# TDA2040_Amp_v2_2.net
KiCad netlist of a schematic drawn in EAGLE
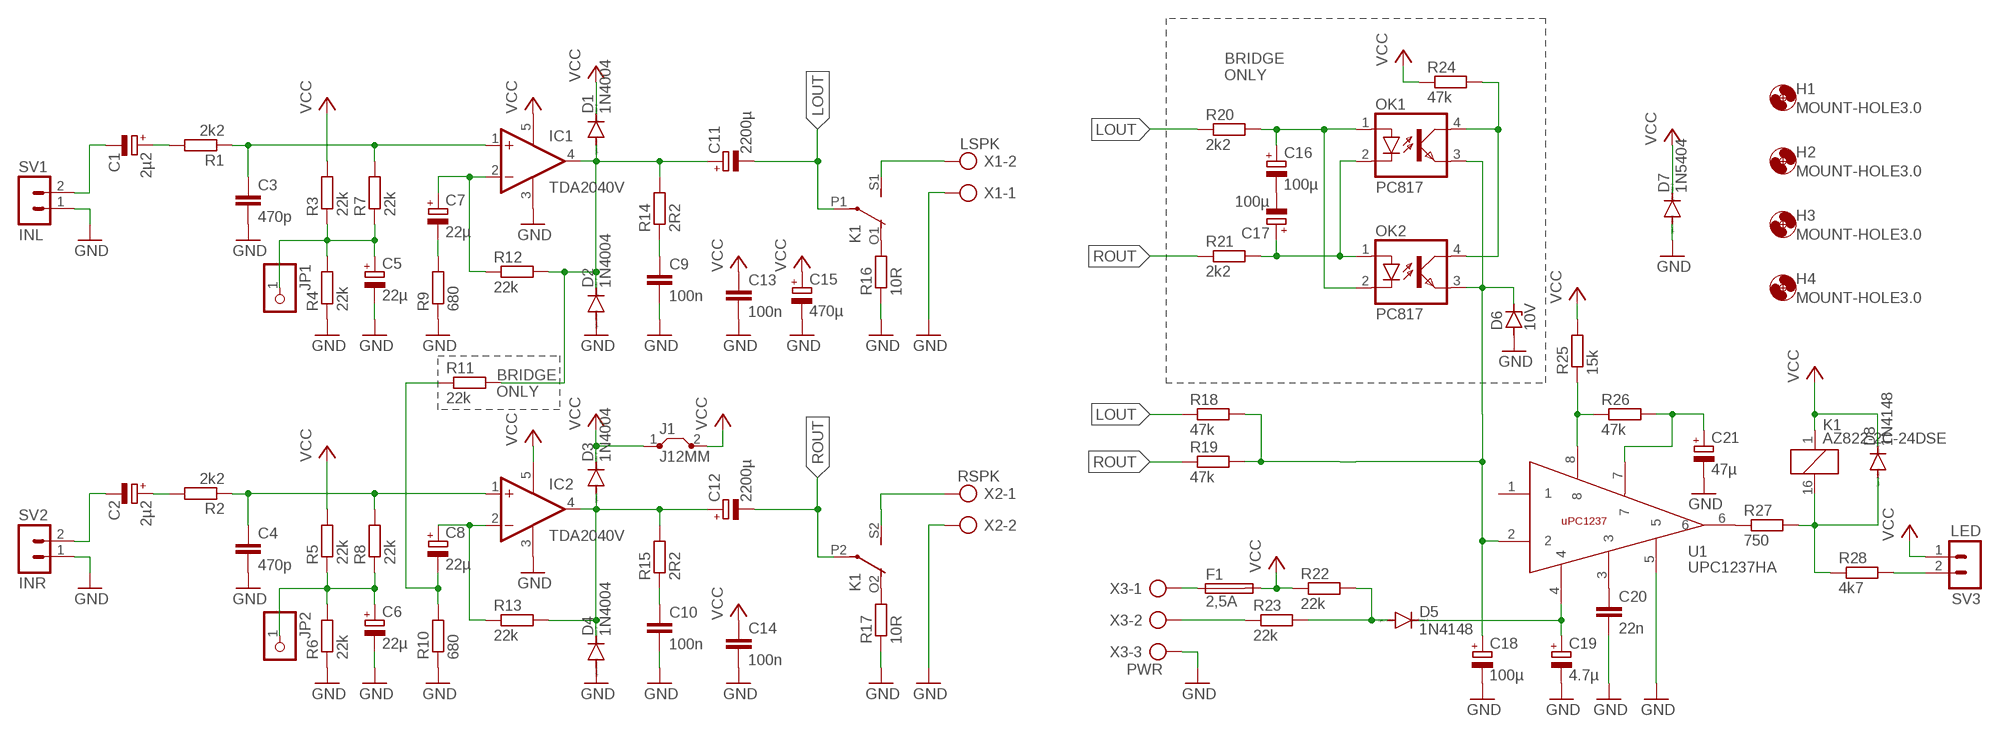
[diagram p0: schematic, sheet 1]

(export (version "E")
  (design (tool "Eeschema 10.0.6"))
  (components
    (comp (ref "C1")
      (value "2µ2")
      (footprint "eagle-import:E2,5-5")
      (libsource (lib "eagle-import") (part "CPOL-EUE2.5-5"))
    )
    (comp (ref "C2")
      (value "2µ2")
      (footprint "eagle-import:E2,5-5")
      (libsource (lib "eagle-import") (part "CPOL-EUE2.5-5"))
    )
    (comp (ref "C3")
      (value "470p")
      (footprint "eagle-import:C050-024X044")
      (libsource (lib "eagle-import") (part "C-EU050-024X044"))
    )
    (comp (ref "C4")
      (value "470p")
      (footprint "eagle-import:C050-024X044")
      (libsource (lib "eagle-import") (part "C-EU050-024X044"))
    )
    (comp (ref "C5")
      (value "22µ")
      (footprint "eagle-import:E2,5-6")
      (libsource (lib "eagle-import") (part "CPOL-EUE2.5-6"))
    )
    (comp (ref "C6")
      (value "22µ")
      (footprint "eagle-import:E2,5-6")
      (libsource (lib "eagle-import") (part "CPOL-EUE2.5-6"))
    )
    (comp (ref "C7")
      (value "22µ")
      (footprint "eagle-import:E2,5-6")
      (libsource (lib "eagle-import") (part "CPOL-EUE2.5-6"))
    )
    (comp (ref "C8")
      (value "22µ")
      (footprint "eagle-import:E2,5-6")
      (libsource (lib "eagle-import") (part "CPOL-EUE2.5-6"))
    )
    (comp (ref "C9")
      (value "100n")
      (footprint "eagle-import:C050-024X044")
      (libsource (lib "eagle-import") (part "C-EU050-024X044"))
    )
    (comp (ref "C10")
      (value "100n")
      (footprint "eagle-import:C050-024X044")
      (libsource (lib "eagle-import") (part "C-EU050-024X044"))
    )
    (comp (ref "C11")
      (value "2200µ")
      (footprint "eagle-import:E5-13")
      (libsource (lib "eagle-import") (part "CPOL-EUE5-13"))
    )
    (comp (ref "C12")
      (value "2200µ")
      (footprint "eagle-import:E5-13")
      (libsource (lib "eagle-import") (part "CPOL-EUE5-13"))
    )
    (comp (ref "C13")
      (value "100n")
      (footprint "eagle-import:C050-024X044")
      (libsource (lib "eagle-import") (part "C-EU050-024X044"))
    )
    (comp (ref "C14")
      (value "100n")
      (footprint "eagle-import:C050-024X044")
      (libsource (lib "eagle-import") (part "C-EU050-024X044"))
    )
    (comp (ref "C15")
      (value "470µ")
      (footprint "eagle-import:E5-13")
      (libsource (lib "eagle-import") (part "CPOL-EUE5-13"))
    )
    (comp (ref "C16")
      (value "100µ")
      (footprint "eagle-import:E2,5-6")
      (libsource (lib "eagle-import") (part "CPOL-EUE2.5-6"))
    )
    (comp (ref "C17")
      (value "100µ")
      (footprint "eagle-import:E2,5-6")
      (libsource (lib "eagle-import") (part "CPOL-EUE2.5-6"))
    )
    (comp (ref "C18")
      (value "100µ")
      (footprint "eagle-import:E2,5-5")
      (libsource (lib "eagle-import") (part "CPOL-EUE2.5-5"))
    )
    (comp (ref "C19")
      (value "4.7µ")
      (footprint "eagle-import:E2,5-5")
      (libsource (lib "eagle-import") (part "CPOL-EUE2.5-5"))
    )
    (comp (ref "C20")
      (value "22n")
      (footprint "eagle-import:C050-024X044")
      (libsource (lib "eagle-import") (part "C-EU050-024X044"))
    )
    (comp (ref "C21")
      (value "47µ")
      (footprint "eagle-import:E2,5-5")
      (libsource (lib "eagle-import") (part "CPOL-EUE2.5-5"))
    )
    (comp (ref "D1")
      (value "1N4004")
      (footprint "eagle-import:DO41-10")
      (libsource (lib "eagle-import") (part "1N4004"))
    )
    (comp (ref "D2")
      (value "1N4004")
      (footprint "eagle-import:DO41-10")
      (libsource (lib "eagle-import") (part "1N4004"))
    )
    (comp (ref "D3")
      (value "1N4004")
      (footprint "eagle-import:DO41-10")
      (libsource (lib "eagle-import") (part "1N4004"))
    )
    (comp (ref "D4")
      (value "1N4004")
      (footprint "eagle-import:DO41-10")
      (libsource (lib "eagle-import") (part "1N4004"))
    )
    (comp (ref "D5")
      (value "1N4148")
      (footprint "eagle-import:DO35-7")
      (libsource (lib "eagle-import") (part "1N4148DO35-7"))
    )
    (comp (ref "D6")
      (value "10V")
      (footprint "eagle-import:DO34Z7")
      (libsource (lib "eagle-import") (part "ZENER-DIODEDO34-7"))
    )
    (comp (ref "D7")
      (value "1N5404")
      (footprint "eagle-import:DO201-15")
      (libsource (lib "eagle-import") (part "1N5400"))
    )
    (comp (ref "D8")
      (value "1N4148")
      (footprint "eagle-import:DO35-7")
      (libsource (lib "eagle-import") (part "1N4148DO35-7"))
    )
    (comp (ref "F1")
      (value "2,5A")
      (footprint "eagle-import:SH22")
      (libsource (lib "eagle-import") (part "SH22"))
    )
    (comp (ref "H1")
      (value "MOUNT-HOLE3.0")
      (footprint "eagle-import:3,0")
      (libsource (lib "eagle-import") (part "MOUNT-HOLE3.0"))
    )
    (comp (ref "H2")
      (value "MOUNT-HOLE3.0")
      (footprint "eagle-import:3,0")
      (libsource (lib "eagle-import") (part "MOUNT-HOLE3.0"))
    )
    (comp (ref "H3")
      (value "MOUNT-HOLE3.0")
      (footprint "eagle-import:3,0")
      (libsource (lib "eagle-import") (part "MOUNT-HOLE3.0"))
    )
    (comp (ref "H4")
      (value "MOUNT-HOLE3.0")
      (footprint "eagle-import:3,0")
      (libsource (lib "eagle-import") (part "MOUNT-HOLE3.0"))
    )
    (comp (ref "IC1")
      (value "TDA2040V")
      (footprint "eagle-import:CB360")
      (libsource (lib "eagle-import") (part "TDA2040V"))
    )
    (comp (ref "IC2")
      (value "TDA2040V")
      (footprint "eagle-import:CB360")
      (libsource (lib "eagle-import") (part "TDA2040V"))
    )
    (comp (ref "J1")
      (value "J12MM")
      (footprint "eagle-import:12")
      (libsource (lib "eagle-import") (part "J12MM"))
    )
    (comp (ref "JP1")
      (value "PINHD-1X1A")
      (footprint "eagle-import:1X01A")
      (libsource (lib "eagle-import") (part "PINHD-1X1A"))
    )
    (comp (ref "JP2")
      (value "PINHD-1X1A")
      (footprint "eagle-import:1X01A")
      (libsource (lib "eagle-import") (part "PINHD-1X1A"))
    )
    (comp (ref "K1")
      (value "AZ822-2C-24DSE")
      (footprint "eagle-import:351")
      (libsource (lib "eagle-import") (part "351"))
    )
    (comp (ref "OK1")
      (value "PC817")
      (footprint "eagle-import:DIL04")
      (fields (field (name "MPN") "PC817X4J000F"))
      (libsource (lib "eagle-import") (part "PC817"))
    )
    (comp (ref "OK2")
      (value "PC817")
      (footprint "eagle-import:DIL04")
      (fields (field (name "MPN") "PC817X4J000F"))
      (libsource (lib "eagle-import") (part "PC817"))
    )
    (comp (ref "R1")
      (value "2k2")
      (footprint "eagle-import:0207_10")
      (libsource (lib "eagle-import") (part "R-EU_0207/10"))
    )
    (comp (ref "R2")
      (value "2k2")
      (footprint "eagle-import:0207_10")
      (libsource (lib "eagle-import") (part "R-EU_0207/10"))
    )
    (comp (ref "R3")
      (value "22k")
      (footprint "eagle-import:0207_10")
      (libsource (lib "eagle-import") (part "R-EU_0207/10"))
    )
    (comp (ref "R4")
      (value "22k")
      (footprint "eagle-import:0207_10")
      (libsource (lib "eagle-import") (part "R-EU_0207/10"))
    )
    (comp (ref "R5")
      (value "22k")
      (footprint "eagle-import:0207_10")
      (libsource (lib "eagle-import") (part "R-EU_0207/10"))
    )
    (comp (ref "R6")
      (value "22k")
      (footprint "eagle-import:0207_10")
      (libsource (lib "eagle-import") (part "R-EU_0207/10"))
    )
    (comp (ref "R7")
      (value "22k")
      (footprint "eagle-import:0207_10")
      (libsource (lib "eagle-import") (part "R-EU_0207/10"))
    )
    (comp (ref "R8")
      (value "22k")
      (footprint "eagle-import:0207_10")
      (libsource (lib "eagle-import") (part "R-EU_0207/10"))
    )
    (comp (ref "R9")
      (value "680")
      (footprint "eagle-import:0207_10")
      (libsource (lib "eagle-import") (part "R-EU_0207/10"))
    )
    (comp (ref "R10")
      (value "680")
      (footprint "eagle-import:0207_10")
      (libsource (lib "eagle-import") (part "R-EU_0207/10"))
    )
    (comp (ref "R11")
      (value "22k")
      (footprint "eagle-import:0207_10")
      (libsource (lib "eagle-import") (part "R-EU_0207/10"))
    )
    (comp (ref "R12")
      (value "22k")
      (footprint "eagle-import:0207_10")
      (libsource (lib "eagle-import") (part "R-EU_0207/10"))
    )
    (comp (ref "R13")
      (value "22k")
      (footprint "eagle-import:0207_10")
      (libsource (lib "eagle-import") (part "R-EU_0207/10"))
    )
    (comp (ref "R14")
      (value "2R2")
      (footprint "eagle-import:0207_10")
      (libsource (lib "eagle-import") (part "R-EU_0207/10"))
    )
    (comp (ref "R15")
      (value "2R2")
      (footprint "eagle-import:0207_10")
      (libsource (lib "eagle-import") (part "R-EU_0207/10"))
    )
    (comp (ref "R16")
      (value "10R")
      (footprint "eagle-import:0207_10")
      (libsource (lib "eagle-import") (part "R-EU_0207/10"))
    )
    (comp (ref "R17")
      (value "10R")
      (footprint "eagle-import:0207_10")
      (libsource (lib "eagle-import") (part "R-EU_0207/10"))
    )
    (comp (ref "R18")
      (value "47k")
      (footprint "eagle-import:0207_10")
      (libsource (lib "eagle-import") (part "R-EU_0207/10"))
    )
    (comp (ref "R19")
      (value "47k")
      (footprint "eagle-import:0207_10")
      (libsource (lib "eagle-import") (part "R-EU_0207/10"))
    )
    (comp (ref "R20")
      (value "2k2")
      (footprint "eagle-import:0207_10")
      (libsource (lib "eagle-import") (part "R-EU_0207/10"))
    )
    (comp (ref "R21")
      (value "2k2")
      (footprint "eagle-import:0207_10")
      (libsource (lib "eagle-import") (part "R-EU_0207/10"))
    )
    (comp (ref "R22")
      (value "22k")
      (footprint "eagle-import:0207_10")
      (libsource (lib "eagle-import") (part "R-EU_0207/10"))
    )
    (comp (ref "R23")
      (value "22k")
      (footprint "eagle-import:0207_10")
      (libsource (lib "eagle-import") (part "R-EU_0207/10"))
    )
    (comp (ref "R24")
      (value "47k")
      (footprint "eagle-import:0207_10")
      (libsource (lib "eagle-import") (part "R-EU_0207/10"))
    )
    (comp (ref "R25")
      (value "15k")
      (footprint "eagle-import:0207_10")
      (libsource (lib "eagle-import") (part "R-EU_0207/10"))
    )
    (comp (ref "R26")
      (value "47k")
      (footprint "eagle-import:0207_10")
      (libsource (lib "eagle-import") (part "R-EU_0207/10"))
    )
    (comp (ref "R27")
      (value "750")
      (footprint "eagle-import:0207_10")
      (libsource (lib "eagle-import") (part "R-EU_0207/10"))
    )
    (comp (ref "R28")
      (value "4k7")
      (footprint "eagle-import:0207_10")
      (libsource (lib "eagle-import") (part "R-EU_0207/10"))
    )
    (comp (ref "SV1")
      (value "INL")
      (footprint "eagle-import:MA02-1")
      (libsource (lib "eagle-import") (part "MA02-1"))
    )
    (comp (ref "SV2")
      (value "INR")
      (footprint "eagle-import:MA02-1")
      (libsource (lib "eagle-import") (part "MA02-1"))
    )
    (comp (ref "SV3")
      (value "LED")
      (footprint "eagle-import:MA02-1")
      (libsource (lib "eagle-import") (part "MA02-1"))
    )
    (comp (ref "U1")
      (value "UPC1237HA")
      (footprint "eagle-import:SIP8")
      (fields (field (name "MF") "NEC"))
      (libsource (lib "eagle-import") (part "UPC1237HA"))
    )
    (comp (ref "X1")
      (value "LSPK")
      (footprint "eagle-import:AK500_2")
      (libsource (lib "eagle-import") (part "AK500/2"))
    )
    (comp (ref "X2")
      (value "RSPK")
      (footprint "eagle-import:AK500_2")
      (libsource (lib "eagle-import") (part "AK500/2"))
    )
    (comp (ref "X3")
      (value "PWR")
      (footprint "eagle-import:AK500_3")
      (libsource (lib "eagle-import") (part "AK500/3"))
    )
  )
  (nets
    (net (code "1") (name "GND") (class "Default")
      (node (ref "C10") (pin "2") (pinfunction "2_2") (pintype "passive"))
      (node (ref "C13") (pin "2") (pinfunction "2_2") (pintype "passive"))
      (node (ref "C14") (pin "2") (pinfunction "2_2") (pintype "passive"))
      (node (ref "C15") (pin "-") (pinfunction "-_-") (pintype "passive"))
      (node (ref "C18") (pin "-") (pinfunction "-_-") (pintype "passive"))
      (node (ref "C19") (pin "-") (pinfunction "-_-") (pintype "passive"))
      (node (ref "C20") (pin "2") (pinfunction "2_2") (pintype "passive"))
      (node (ref "C21") (pin "-") (pinfunction "-_-") (pintype "passive"))
      (node (ref "C3") (pin "2") (pinfunction "2_2") (pintype "passive"))
      (node (ref "C4") (pin "2") (pinfunction "2_2") (pintype "passive"))
      (node (ref "C5") (pin "-") (pinfunction "-_-") (pintype "passive"))
      (node (ref "C6") (pin "-") (pinfunction "-_-") (pintype "passive"))
      (node (ref "C9") (pin "2") (pinfunction "2_2") (pintype "passive"))
      (node (ref "D2") (pin "A") (pinfunction "A_A") (pintype "passive"))
      (node (ref "D4") (pin "A") (pinfunction "A_A") (pintype "passive"))
      (node (ref "D6") (pin "A") (pinfunction "A_A") (pintype "passive"))
      (node (ref "D7") (pin "A") (pinfunction "A_A") (pintype "passive"))
      (node (ref "IC1") (pin "3") (pinfunction "V-_3") (pintype "power_in"))
      (node (ref "IC2") (pin "3") (pinfunction "V-_3") (pintype "power_in"))
      (node (ref "R10") (pin "1") (pinfunction "1_1") (pintype "passive"))
      (node (ref "R16") (pin "1") (pinfunction "1_1") (pintype "passive"))
      (node (ref "R17") (pin "1") (pinfunction "1_1") (pintype "passive"))
      (node (ref "R4") (pin "1") (pinfunction "1_1") (pintype "passive"))
      (node (ref "R6") (pin "1") (pinfunction "1_1") (pintype "passive"))
      (node (ref "R9") (pin "1") (pinfunction "1_1") (pintype "passive"))
      (node (ref "SV1") (pin "1") (pinfunction "1_1") (pintype "passive"))
      (node (ref "SV2") (pin "1") (pinfunction "1_1") (pintype "passive"))
      (node (ref "U1") (pin "5") (pinfunction "5_5") (pintype "bidirectional"))
      (node (ref "X1") (pin "1") (pinfunction "KL_1") (pintype "passive"))
      (node (ref "X2") (pin "2") (pinfunction "KL_2") (pintype "passive"))
      (node (ref "X3") (pin "3") (pinfunction "KL_3") (pintype "passive"))
    )
    (net (code "2") (name "LOUT") (class "Default")
      (node (ref "C11") (pin "-") (pinfunction "-_-") (pintype "passive"))
      (node (ref "K1") (pin "P1") (pinfunction "P_P1") (pintype "passive"))
      (node (ref "R18") (pin "1") (pinfunction "1_1") (pintype "passive"))
      (node (ref "R20") (pin "1") (pinfunction "1_1") (pintype "passive"))
    )
    (net (code "3") (name "Net-(C1-Pad+)") (class "Default")
      (node (ref "C1") (pin "+") (pinfunction "+_+") (pintype "passive"))
      (node (ref "R1") (pin "2") (pinfunction "2_2") (pintype "passive"))
    )
    (net (code "4") (name "Net-(C1-Pad-)") (class "Default")
      (node (ref "C1") (pin "-") (pinfunction "-_-") (pintype "passive"))
      (node (ref "SV1") (pin "2") (pinfunction "2_2") (pintype "passive"))
    )
    (net (code "5") (name "Net-(C2-Pad+)") (class "Default")
      (node (ref "C2") (pin "+") (pinfunction "+_+") (pintype "passive"))
      (node (ref "R2") (pin "2") (pinfunction "2_2") (pintype "passive"))
    )
    (net (code "6") (name "Net-(C2-Pad-)") (class "Default")
      (node (ref "C2") (pin "-") (pinfunction "-_-") (pintype "passive"))
      (node (ref "SV2") (pin "2") (pinfunction "2_2") (pintype "passive"))
    )
    (net (code "7") (name "Net-(C5-Pad+)") (class "Default")
      (node (ref "C5") (pin "+") (pinfunction "+_+") (pintype "passive"))
      (node (ref "JP1") (pin "1") (pinfunction "1_1") (pintype "passive"))
      (node (ref "R3") (pin "1") (pinfunction "1_1") (pintype "passive"))
      (node (ref "R4") (pin "2") (pinfunction "2_2") (pintype "passive"))
      (node (ref "R7") (pin "1") (pinfunction "1_1") (pintype "passive"))
    )
    (net (code "8") (name "Net-(C6-Pad+)") (class "Default")
      (node (ref "C6") (pin "+") (pinfunction "+_+") (pintype "passive"))
      (node (ref "JP2") (pin "1") (pinfunction "1_1") (pintype "passive"))
      (node (ref "R5") (pin "1") (pinfunction "1_1") (pintype "passive"))
      (node (ref "R6") (pin "2") (pinfunction "2_2") (pintype "passive"))
      (node (ref "R8") (pin "1") (pinfunction "1_1") (pintype "passive"))
    )
    (net (code "9") (name "Net-(C7-Pad-)") (class "Default")
      (node (ref "C7") (pin "-") (pinfunction "-_-") (pintype "passive"))
      (node (ref "R9") (pin "2") (pinfunction "2_2") (pintype "passive"))
    )
    (net (code "10") (name "Net-(C8-Pad-)") (class "Default")
      (node (ref "C8") (pin "-") (pinfunction "-_-") (pintype "passive"))
      (node (ref "R10") (pin "2") (pinfunction "2_2") (pintype "passive"))
      (node (ref "R11") (pin "1") (pinfunction "1_1") (pintype "passive"))
    )
    (net (code "11") (name "Net-(C9-Pad1)") (class "Default")
      (node (ref "C9") (pin "1") (pinfunction "1_1") (pintype "passive"))
      (node (ref "R14") (pin "1") (pinfunction "1_1") (pintype "passive"))
    )
    (net (code "12") (name "Net-(C10-Pad1)") (class "Default")
      (node (ref "C10") (pin "1") (pinfunction "1_1") (pintype "passive"))
      (node (ref "R15") (pin "1") (pinfunction "1_1") (pintype "passive"))
    )
    (net (code "13") (name "Net-(C16-Pad-)") (class "Default")
      (node (ref "C16") (pin "-") (pinfunction "-_-") (pintype "passive"))
      (node (ref "C17") (pin "-") (pinfunction "-_-") (pintype "passive"))
    )
    (net (code "14") (name "Net-(C19-Pad+)") (class "Default")
      (node (ref "C19") (pin "+") (pinfunction "+_+") (pintype "passive"))
      (node (ref "D5") (pin "C") (pinfunction "C_C") (pintype "passive"))
      (node (ref "U1") (pin "4") (pinfunction "4_4") (pintype "bidirectional"))
    )
    (net (code "15") (name "Net-(C20-Pad1)") (class "Default")
      (node (ref "C20") (pin "1") (pinfunction "1_1") (pintype "passive"))
      (node (ref "U1") (pin "3") (pinfunction "3_3") (pintype "bidirectional"))
    )
    (net (code "16") (name "Net-(C21-Pad+)") (class "Default")
      (node (ref "C21") (pin "+") (pinfunction "+_+") (pintype "passive"))
      (node (ref "R26") (pin "2") (pinfunction "2_2") (pintype "passive"))
      (node (ref "U1") (pin "7") (pinfunction "7_7") (pintype "bidirectional"))
    )
    (net (code "17") (name "Net-(D5-PadA)") (class "Default")
      (node (ref "D5") (pin "A") (pinfunction "A_A") (pintype "passive"))
      (node (ref "R22") (pin "2") (pinfunction "2_2") (pintype "passive"))
      (node (ref "R23") (pin "2") (pinfunction "2_2") (pintype "passive"))
    )
    (net (code "18") (name "Net-(IC1-+IN)") (class "Default")
      (node (ref "C3") (pin "1") (pinfunction "1_1") (pintype "passive"))
      (node (ref "IC1") (pin "1") (pinfunction "+IN_1") (pintype "input"))
      (node (ref "R1") (pin "1") (pinfunction "1_1") (pintype "passive"))
      (node (ref "R7") (pin "2") (pinfunction "2_2") (pintype "passive"))
    )
    (net (code "19") (name "Net-(IC1--IN)") (class "Default")
      (node (ref "C7") (pin "+") (pinfunction "+_+") (pintype "passive"))
      (node (ref "IC1") (pin "2") (pinfunction "-IN_2") (pintype "input"))
      (node (ref "R12") (pin "1") (pinfunction "1_1") (pintype "passive"))
    )
    (net (code "20") (name "Net-(IC1-OUT)") (class "Default")
      (node (ref "C11") (pin "+") (pinfunction "+_+") (pintype "passive"))
      (node (ref "D1") (pin "A") (pinfunction "A_A") (pintype "passive"))
      (node (ref "D2") (pin "C") (pinfunction "C_C") (pintype "passive"))
      (node (ref "IC1") (pin "4") (pinfunction "OUT_4") (pintype "output"))
      (node (ref "R11") (pin "2") (pinfunction "2_2") (pintype "passive"))
      (node (ref "R12") (pin "2") (pinfunction "2_2") (pintype "passive"))
      (node (ref "R14") (pin "2") (pinfunction "2_2") (pintype "passive"))
    )
    (net (code "21") (name "Net-(IC2-+IN)") (class "Default")
      (node (ref "C4") (pin "1") (pinfunction "1_1") (pintype "passive"))
      (node (ref "IC2") (pin "1") (pinfunction "+IN_1") (pintype "input"))
      (node (ref "R2") (pin "1") (pinfunction "1_1") (pintype "passive"))
      (node (ref "R8") (pin "2") (pinfunction "2_2") (pintype "passive"))
    )
    (net (code "22") (name "Net-(IC2--IN)") (class "Default")
      (node (ref "C8") (pin "+") (pinfunction "+_+") (pintype "passive"))
      (node (ref "IC2") (pin "2") (pinfunction "-IN_2") (pintype "input"))
      (node (ref "R13") (pin "1") (pinfunction "1_1") (pintype "passive"))
    )
    (net (code "23") (name "Net-(IC2-OUT)") (class "Default")
      (node (ref "C12") (pin "+") (pinfunction "+_+") (pintype "passive"))
      (node (ref "D3") (pin "A") (pinfunction "A_A") (pintype "passive"))
      (node (ref "D4") (pin "C") (pinfunction "C_C") (pintype "passive"))
      (node (ref "IC2") (pin "4") (pinfunction "OUT_4") (pintype "output"))
      (node (ref "R13") (pin "2") (pinfunction "2_2") (pintype "passive"))
      (node (ref "R15") (pin "2") (pinfunction "2_2") (pintype "passive"))
    )
    (net (code "24") (name "Net-(K1A-2)") (class "Default")
      (node (ref "D8") (pin "A") (pinfunction "A_A") (pintype "passive"))
      (node (ref "K1") (pin "16") (pinfunction "2_16") (pintype "passive"))
      (node (ref "R27") (pin "2") (pinfunction "2_2") (pintype "passive"))
      (node (ref "R28") (pin "1") (pinfunction "1_1") (pintype "passive"))
    )
    (net (code "25") (name "Net-(K1B-O)") (class "Default")
      (node (ref "K1") (pin "O1") (pinfunction "O_O1") (pintype "passive"))
      (node (ref "R16") (pin "2") (pinfunction "2_2") (pintype "passive"))
    )
    (net (code "26") (name "Net-(K1B-S)") (class "Default")
      (node (ref "K1") (pin "S1") (pinfunction "S_S1") (pintype "passive"))
      (node (ref "X1") (pin "2") (pinfunction "KL_2") (pintype "passive"))
    )
    (net (code "27") (name "Net-(K1C-O)") (class "Default")
      (node (ref "K1") (pin "O2") (pinfunction "O_O2") (pintype "passive"))
      (node (ref "R17") (pin "2") (pinfunction "2_2") (pintype "passive"))
    )
    (net (code "28") (name "Net-(K1C-S)") (class "Default")
      (node (ref "K1") (pin "S2") (pinfunction "S_S2") (pintype "passive"))
      (node (ref "X2") (pin "1") (pinfunction "KL_1") (pintype "passive"))
    )
    (net (code "29") (name "Net-(OK1-A)") (class "Default")
      (node (ref "C16") (pin "+") (pinfunction "+_+") (pintype "passive"))
      (node (ref "OK1") (pin "1") (pinfunction "A_1") (pintype "passive"))
      (node (ref "OK2") (pin "2") (pinfunction "C_2") (pintype "passive"))
      (node (ref "R20") (pin "2") (pinfunction "2_2") (pintype "passive"))
    )
    (net (code "30") (name "Net-(OK1-C)") (class "Default")
      (node (ref "C17") (pin "+") (pinfunction "+_+") (pintype "passive"))
      (node (ref "OK1") (pin "2") (pinfunction "C_2") (pintype "passive"))
      (node (ref "OK2") (pin "1") (pinfunction "A_1") (pintype "passive"))
      (node (ref "R21") (pin "2") (pinfunction "2_2") (pintype "passive"))
    )
    (net (code "31") (name "Net-(OK1-COL)") (class "Default")
      (node (ref "OK1") (pin "4") (pinfunction "COL_4") (pintype "passive"))
      (node (ref "OK2") (pin "4") (pinfunction "COL_4") (pintype "passive"))
      (node (ref "R24") (pin "2") (pinfunction "2_2") (pintype "passive"))
    )
    (net (code "32") (name "Net-(OK1-EMIT)") (class "Default")
      (node (ref "C18") (pin "+") (pinfunction "+_+") (pintype "passive"))
      (node (ref "D6") (pin "C") (pinfunction "C_C") (pintype "passive"))
      (node (ref "OK1") (pin "3") (pinfunction "EMIT_3") (pintype "passive"))
      (node (ref "OK2") (pin "3") (pinfunction "EMIT_3") (pintype "passive"))
      (node (ref "R18") (pin "2") (pinfunction "2_2") (pintype "passive"))
      (node (ref "R19") (pin "2") (pinfunction "2_2") (pintype "passive"))
      (node (ref "U1") (pin "2") (pinfunction "2_2") (pintype "bidirectional"))
    )
    (net (code "33") (name "Net-(R25-Pad1)") (class "Default")
      (node (ref "R25") (pin "1") (pinfunction "1_1") (pintype "passive"))
      (node (ref "R26") (pin "1") (pinfunction "1_1") (pintype "passive"))
      (node (ref "U1") (pin "8") (pinfunction "8_8") (pintype "bidirectional"))
    )
    (net (code "34") (name "Net-(R27-Pad1)") (class "Default")
      (node (ref "R27") (pin "1") (pinfunction "1_1") (pintype "passive"))
      (node (ref "U1") (pin "6") (pinfunction "6_6") (pintype "bidirectional"))
    )
    (net (code "35") (name "Net-(R28-Pad2)") (class "Default")
      (node (ref "R28") (pin "2") (pinfunction "2_2") (pintype "passive"))
      (node (ref "SV3") (pin "2") (pinfunction "2_2") (pintype "passive"))
    )
    (net (code "36") (name "Net-(X3A-KL)") (class "Default")
      (node (ref "F1") (pin "1") (pinfunction "1_1") (pintype "passive"))
      (node (ref "X3") (pin "1") (pinfunction "KL_1") (pintype "passive"))
    )
    (net (code "37") (name "Net-(X3B-KL)") (class "Default")
      (node (ref "R23") (pin "1") (pinfunction "1_1") (pintype "passive"))
      (node (ref "X3") (pin "2") (pinfunction "KL_2") (pintype "passive"))
    )
    (net (code "38") (name "ROUT") (class "Default")
      (node (ref "C12") (pin "-") (pinfunction "-_-") (pintype "passive"))
      (node (ref "K1") (pin "P2") (pinfunction "P_P2") (pintype "passive"))
      (node (ref "R19") (pin "1") (pinfunction "1_1") (pintype "passive"))
      (node (ref "R21") (pin "1") (pinfunction "1_1") (pintype "passive"))
    )
    (net (code "39") (name "VCC") (class "Default")
      (node (ref "C13") (pin "1") (pinfunction "1_1") (pintype "passive"))
      (node (ref "C14") (pin "1") (pinfunction "1_1") (pintype "passive"))
      (node (ref "C15") (pin "+") (pinfunction "+_+") (pintype "passive"))
      (node (ref "D1") (pin "C") (pinfunction "C_C") (pintype "passive"))
      (node (ref "D3") (pin "C") (pinfunction "C_C") (pintype "passive"))
      (node (ref "D7") (pin "C") (pinfunction "C_C") (pintype "passive"))
      (node (ref "D8") (pin "C") (pinfunction "C_C") (pintype "passive"))
      (node (ref "F1") (pin "2") (pinfunction "2_2") (pintype "passive"))
      (node (ref "IC1") (pin "5") (pinfunction "V+_5") (pintype "power_in"))
      (node (ref "IC2") (pin "5") (pinfunction "V+_5") (pintype "power_in"))
      (node (ref "J1") (pin "1") (pinfunction "1_1") (pintype "passive"))
      (node (ref "J1") (pin "2") (pinfunction "2_2") (pintype "passive"))
      (node (ref "K1") (pin "1") (pinfunction "1_1") (pintype "passive"))
      (node (ref "R22") (pin "1") (pinfunction "1_1") (pintype "passive"))
      (node (ref "R24") (pin "1") (pinfunction "1_1") (pintype "passive"))
      (node (ref "R25") (pin "2") (pinfunction "2_2") (pintype "passive"))
      (node (ref "R3") (pin "2") (pinfunction "2_2") (pintype "passive"))
      (node (ref "R5") (pin "2") (pinfunction "2_2") (pintype "passive"))
      (node (ref "SV3") (pin "1") (pinfunction "1_1") (pintype "passive"))
    )
    (net (code "40") (name "unconnected-(U1-Pad1)") (class "Default")
      (node (ref "U1") (pin "1") (pinfunction "1_1") (pintype "bidirectional"))
    )
  )
)
